# Telemetria.net
KiCad netlist of a schematic drawn in Altium Designer
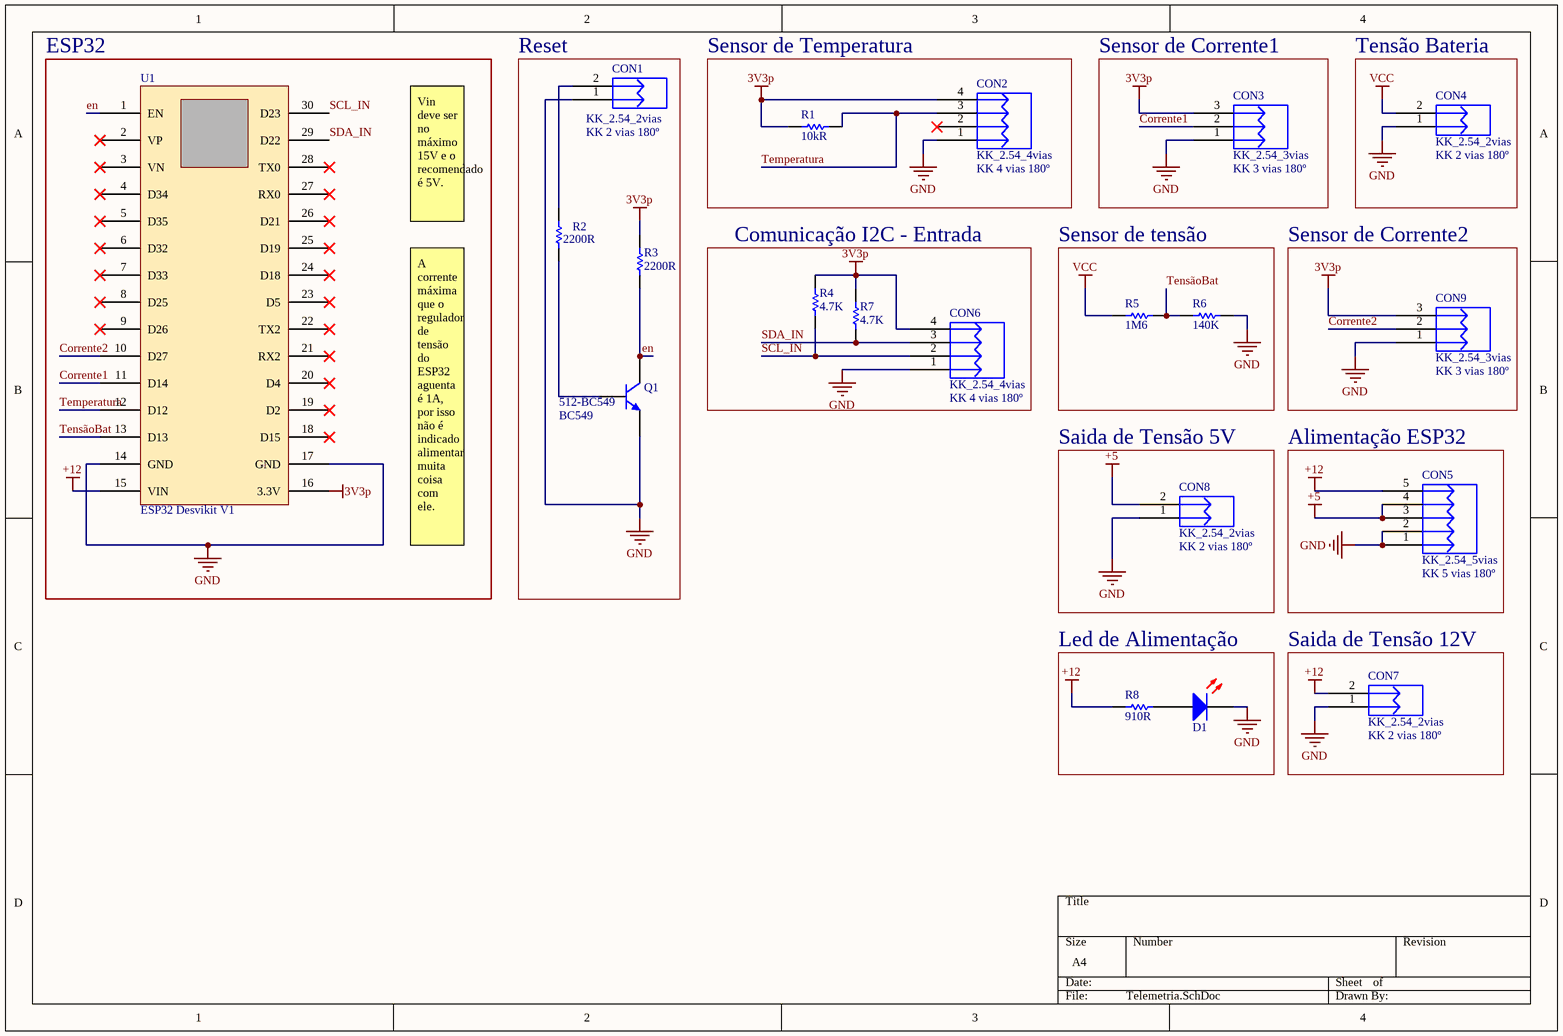
[diagram p0: Telemetria.SchDoc]

(export (version "E")
  (design (tool "Eeschema 10.0.6"))
  (components
    (comp (ref "CON1")
      (value "KK_2.54_2vias")
      (footprint "KK_2VIAS_180º")
      (description "Conector KK 2.54mm 2 vias")
      (fields (field (name "VALOR") "KK 2 vias 180º"))
      (libsource (lib "Conectores_Sch") (part "KK_2.54_2vias"))
    )
    (comp (ref "CON2")
      (value "KK_2.54_4vias")
      (footprint "KK_4vias_180°")
      (description "Conector KK 2.54mm 4 vias")
      (fields (field (name "VALOR") "KK 4 vias 180º"))
      (libsource (lib "Conectores_Sch") (part "KK_2.54_4vias"))
    )
    (comp (ref "CON3")
      (value "KK_2.54_3vias")
      (footprint "KK_3vias_180º")
      (description "Conector KK 2.54mm 3 vias")
      (fields (field (name "VALOR") "KK 3 vias 180º"))
      (libsource (lib "Conectores_Sch") (part "KK_2.54_3vias"))
    )
    (comp (ref "CON4")
      (value "KK_2.54_2vias")
      (footprint "KK_2VIAS_180º")
      (description "Conector KK 2.54mm 2 vias")
      (fields (field (name "VALOR") "KK 2 vias 180º"))
      (libsource (lib "Conectores_Sch") (part "KK_2.54_2vias"))
    )
    (comp (ref "CON5")
      (value "KK_2.54_5vias")
      (footprint "KK_5vias_180°")
      (description "Conector KK 2.54mm 5 vias")
      (fields (field (name "VALOR") "KK 5 vias 180º"))
      (libsource (lib "Conectores_Sch") (part "KK_2.54_5vias"))
    )
    (comp (ref "CON6")
      (value "KK_2.54_4vias")
      (footprint "KK_4vias_180°")
      (description "Conector KK 2.54mm 4 vias")
      (fields (field (name "VALOR") "KK 4 vias 180º"))
      (libsource (lib "Conectores_Sch") (part "KK_2.54_4vias"))
    )
    (comp (ref "CON7")
      (value "KK_2.54_2vias")
      (footprint "KK_2VIAS_180º")
      (description "Conector KK 2.54mm 2 vias")
      (fields (field (name "VALOR") "KK 2 vias 180º"))
      (libsource (lib "Conectores_Sch") (part "KK_2.54_2vias"))
    )
    (comp (ref "CON8")
      (value "KK_2.54_2vias")
      (footprint "KK_2VIAS_180º")
      (description "Conector KK 2.54mm 2 vias")
      (fields (field (name "VALOR") "KK 2 vias 180º"))
      (libsource (lib "Conectores_Sch") (part "KK_2.54_2vias"))
    )
    (comp (ref "CON9")
      (value "KK_2.54_3vias")
      (footprint "KK_3vias_180º")
      (description "Conector KK 2.54mm 3 vias")
      (fields (field (name "VALOR") "KK 3 vias 180º"))
      (libsource (lib "Conectores_Sch") (part "KK_2.54_3vias"))
    )
    (comp (ref "D1")
      (value "LED 5MM RED")
      (footprint "LED 5MM RED")
      (fields (field (name "MANUFACTURER") "Paralight") (field (name "MANUFACTURER PART NUMBER") "IMP585"))
      (libsource (lib "esp32") (part "LED 5MM RED"))
    )
    (comp (ref "Q1")
      (value "BC549")
      (footprint "TO92")
      (description "TRANS NPN 30V 0.1A TO-92")
      (fields
        (field (name "MANUFACTURER") "Fairchild Semiconductor")
        (field (name "SUPPLIER PART NUMBER 1") "512-BC549")
      )
      (libsource (lib "PS_Balanca") (part "BC549"))
    )
    (comp (ref "R1")
      (value "RES 470R 1/4W CARBON FILM")
      (footprint "RES 470R 1/4W CARBON FILM")
      (description "RES 470R OHM 1/4W 5% CARBON FILM")
      (fields
        (field (name "MANUFACTURER") "Ty-Ohm")
        (field (name "MANUFACTURER PART NUMBER") "CR25")
        (field (name "RESISTANCE (OHMS)") "10kR")
      )
      (libsource (lib "esp32") (part "RES 470R 1/4W CARBON FILM"))
    )
    (comp (ref "R2")
      (value "RES 470R 1/4W CARBON FILM")
      (footprint "RES 470R 1/4W CARBON FILM")
      (description "RES 470R OHM 1/4W 5% CARBON FILM")
      (fields
        (field (name "MANUFACTURER") "Ty-Ohm")
        (field (name "MANUFACTURER PART NUMBER") "CR25")
        (field (name "RESISTANCE (OHMS)") "2200R")
      )
      (libsource (lib "esp32") (part "RES 470R 1/4W CARBON FILM"))
    )
    (comp (ref "R3")
      (value "RES 470R 1/4W CARBON FILM")
      (footprint "RES 470R 1/4W CARBON FILM")
      (description "RES 470R OHM 1/4W 5% CARBON FILM")
      (fields
        (field (name "MANUFACTURER") "Ty-Ohm")
        (field (name "MANUFACTURER PART NUMBER") "CR25")
        (field (name "RESISTANCE (OHMS)") "2200R")
      )
      (libsource (lib "esp32") (part "RES 470R 1/4W CARBON FILM"))
    )
    (comp (ref "R4")
      (value "4.7K")
      (footprint "RES 4.7K 1/4W CARBON FILM")
      (description "RES 4.7K OHM 1/4W 5% CARBON FILM")
      (fields (field (name "MANUFACTURER") "Ty-Ohm") (field (name "MANUFACTURER PART NUMBER") "CR25"))
      (libsource (lib "esp32") (part "RES 4.7K 1/4W CARBON FILM"))
    )
    (comp (ref "R5")
      (value "1M6")
      (footprint "RESISTOR 0603")
      (fields
        (field (name "MANUFACTURER") "PANASONIC ELECTRONIC COMPONENTS")
        (field (name "MANUFACTURER PART NUMBER") "ERJ-3GEY0R00V")
        (field (name "TOLERANCE") "Jumper")
      )
      (libsource (lib "Resistores_SCHLIB") (part "RES 0R 5% 0603"))
    )
    (comp (ref "R6")
      (value "140K")
      (footprint "RESISTOR 0805")
      (fields
        (field (name "MANUFACTURER") "Panasonic")
        (field (name "MANUFACTURER PART NUMBER") "ERJP06F2200V")
      )
      (libsource (lib "Resistores_SCHLIB") (part "RES 220R 0805"))
    )
    (comp (ref "R7")
      (value "4.7K")
      (footprint "RES 4.7K 1/4W CARBON FILM")
      (description "RES 4.7K OHM 1/4W 5% CARBON FILM")
      (fields (field (name "MANUFACTURER") "Ty-Ohm") (field (name "MANUFACTURER PART NUMBER") "CR25"))
      (libsource (lib "esp32") (part "RES 4.7K 1/4W CARBON FILM"))
    )
    (comp (ref "R8")
      (value "RES 470R 1/4W CARBON FILM")
      (footprint "RES 470R 1/4W CARBON FILM")
      (description "RES 470R OHM 1/4W 5% CARBON FILM")
      (fields
        (field (name "MANUFACTURER") "Ty-Ohm")
        (field (name "MANUFACTURER PART NUMBER") "CR25")
        (field (name "RESISTANCE (OHMS)") "910R")
      )
      (libsource (lib "esp32") (part "RES 470R 1/4W CARBON FILM"))
    )
    (comp (ref "U1")
      (value "ESP32 Desvikit V1")
      (footprint "ESP32_Desvikit_v1")
      (description "microcontrolador com moculo bluethoth e wifi")
      (fields (field (name "Comment") "microcontrolador"))
      (libsource (lib "esp32") (part "ESP32 Desvikit v1"))
    )
  )
  (nets
    (net (code "1") (name "+5") (class "Default")
      (node (ref "CON5") (pin "3") (pintype "passive"))
      (node (ref "CON5") (pin "4") (pintype "passive"))
      (node (ref "CON8") (pin "2") (pintype "passive"))
    )
    (net (code "2") (name "+12") (class "Default")
      (node (ref "CON5") (pin "5") (pintype "passive"))
      (node (ref "CON7") (pin "2") (pintype "passive"))
      (node (ref "R8") (pin "2") (pinfunction "2_2") (pintype "passive"))
      (node (ref "U1") (pin "15") (pinfunction "VIN_15") (pintype "passive"))
    )
    (net (code "3") (name "/Corrente1") (class "Default")
      (node (ref "CON3") (pin "2") (pintype "passive"))
      (node (ref "U1") (pin "11") (pinfunction "D14_11") (pintype "passive"))
    )
    (net (code "4") (name "/Corrente2") (class "Default")
      (node (ref "CON9") (pin "2") (pintype "passive"))
      (node (ref "U1") (pin "10") (pinfunction "D27_10") (pintype "passive"))
    )
    (net (code "5") (name "/SCL_IN") (class "Default")
      (node (ref "CON6") (pin "2") (pintype "passive"))
      (node (ref "R4") (pin "2") (pinfunction "2_2") (pintype "passive"))
      (node (ref "U1") (pin "30") (pinfunction "D23_30") (pintype "passive"))
    )
    (net (code "6") (name "/SDA_IN") (class "Default")
      (node (ref "CON6") (pin "3") (pintype "passive"))
      (node (ref "R7") (pin "2") (pinfunction "2_2") (pintype "passive"))
      (node (ref "U1") (pin "29") (pinfunction "D22_29") (pintype "passive"))
    )
    (net (code "7") (name "/Temperatura") (class "Default")
      (node (ref "CON2") (pin "3") (pintype "passive"))
      (node (ref "R1") (pin "2") (pinfunction "2_2") (pintype "passive"))
      (node (ref "U1") (pin "12") (pinfunction "D12_12") (pintype "passive"))
    )
    (net (code "8") (name "/TensãoBat") (class "Default")
      (node (ref "R5") (pin "2") (pinfunction "2_2") (pintype "passive"))
      (node (ref "R6") (pin "1") (pinfunction "1_1") (pintype "passive"))
      (node (ref "U1") (pin "13") (pinfunction "D13_13") (pintype "passive"))
    )
    (net (code "9") (name "/en") (class "Default")
      (node (ref "Q1") (pin "1") (pinfunction "C_1") (pintype "passive"))
      (node (ref "R3") (pin "1") (pinfunction "1_1") (pintype "passive"))
      (node (ref "U1") (pin "1") (pinfunction "EN_1") (pintype "passive"))
    )
    (net (code "10") (name "3V3p") (class "Default")
      (node (ref "CON2") (pin "4") (pintype "passive"))
      (node (ref "CON3") (pin "3") (pintype "passive"))
      (node (ref "CON6") (pin "4") (pintype "passive"))
      (node (ref "CON9") (pin "3") (pintype "passive"))
      (node (ref "R1") (pin "1") (pinfunction "1_1") (pintype "passive"))
      (node (ref "R3") (pin "2") (pinfunction "2_2") (pintype "passive"))
      (node (ref "R4") (pin "1") (pinfunction "1_1") (pintype "passive"))
      (node (ref "R7") (pin "1") (pinfunction "1_1") (pintype "passive"))
      (node (ref "U1") (pin "16") (pinfunction "3.3V_16") (pintype "passive"))
    )
    (net (code "11") (name "GND") (class "Default")
      (node (ref "CON1") (pin "1") (pintype "passive"))
      (node (ref "CON2") (pin "1") (pintype "passive"))
      (node (ref "CON3") (pin "1") (pintype "passive"))
      (node (ref "CON4") (pin "1") (pintype "passive"))
      (node (ref "CON5") (pin "1") (pintype "passive"))
      (node (ref "CON5") (pin "2") (pintype "passive"))
      (node (ref "CON6") (pin "1") (pintype "passive"))
      (node (ref "CON7") (pin "1") (pintype "passive"))
      (node (ref "CON8") (pin "1") (pintype "passive"))
      (node (ref "CON9") (pin "1") (pintype "passive"))
      (node (ref "D1") (pin "2") (pinfunction "K_2") (pintype "passive"))
      (node (ref "Q1") (pin "3") (pinfunction "E_3") (pintype "passive"))
      (node (ref "R6") (pin "2") (pinfunction "2_2") (pintype "passive"))
      (node (ref "U1") (pin "14") (pinfunction "GND_14") (pintype "passive"))
      (node (ref "U1") (pin "17") (pinfunction "GND_17") (pintype "passive"))
    )
    (net (code "12") (name "Net-(CON1-Pad2)") (class "Default")
      (node (ref "CON1") (pin "2") (pintype "passive"))
      (node (ref "R2") (pin "2") (pinfunction "2_2") (pintype "passive"))
    )
    (net (code "13") (name "Net-(D1-A)") (class "Default")
      (node (ref "D1") (pin "1") (pinfunction "A_1") (pintype "passive"))
      (node (ref "R8") (pin "1") (pinfunction "1_1") (pintype "passive"))
    )
    (net (code "14") (name "Net-(Q1-B)") (class "Default")
      (node (ref "Q1") (pin "2") (pinfunction "B_2") (pintype "passive"))
      (node (ref "R2") (pin "1") (pinfunction "1_1") (pintype "passive"))
    )
    (net (code "15") (name "VCC") (class "Default")
      (node (ref "CON4") (pin "2") (pintype "passive"))
      (node (ref "R5") (pin "1") (pinfunction "1_1") (pintype "passive"))
    )
    (net (code "16") (name "unconnected-(CON2-Pad2)") (class "Default")
      (node (ref "CON2") (pin "2") (pintype "passive+no_connect"))
    )
    (net (code "17") (name "unconnected-(U1-D2-Pad19)") (class "Default")
      (node (ref "U1") (pin "19") (pinfunction "D2_19") (pintype "passive+no_connect"))
    )
    (net (code "18") (name "unconnected-(U1-D4-Pad20)") (class "Default")
      (node (ref "U1") (pin "20") (pinfunction "D4_20") (pintype "passive+no_connect"))
    )
    (net (code "19") (name "unconnected-(U1-D5-Pad23)") (class "Default")
      (node (ref "U1") (pin "23") (pinfunction "D5_23") (pintype "passive+no_connect"))
    )
    (net (code "20") (name "unconnected-(U1-D15-Pad18)") (class "Default")
      (node (ref "U1") (pin "18") (pinfunction "D15_18") (pintype "passive+no_connect"))
    )
    (net (code "21") (name "unconnected-(U1-D18-Pad24)") (class "Default")
      (node (ref "U1") (pin "24") (pinfunction "D18_24") (pintype "passive+no_connect"))
    )
    (net (code "22") (name "unconnected-(U1-D19-Pad25)") (class "Default")
      (node (ref "U1") (pin "25") (pinfunction "D19_25") (pintype "passive+no_connect"))
    )
    (net (code "23") (name "unconnected-(U1-D21-Pad26)") (class "Default")
      (node (ref "U1") (pin "26") (pinfunction "D21_26") (pintype "passive+no_connect"))
    )
    (net (code "24") (name "unconnected-(U1-D25-Pad8)") (class "Default")
      (node (ref "U1") (pin "8") (pinfunction "D25_8") (pintype "passive+no_connect"))
    )
    (net (code "25") (name "unconnected-(U1-D26-Pad9)") (class "Default")
      (node (ref "U1") (pin "9") (pinfunction "D26_9") (pintype "passive+no_connect"))
    )
    (net (code "26") (name "unconnected-(U1-D32-Pad6)") (class "Default")
      (node (ref "U1") (pin "6") (pinfunction "D32_6") (pintype "passive+no_connect"))
    )
    (net (code "27") (name "unconnected-(U1-D33-Pad7)") (class "Default")
      (node (ref "U1") (pin "7") (pinfunction "D33_7") (pintype "passive+no_connect"))
    )
    (net (code "28") (name "unconnected-(U1-D34-Pad4)") (class "Default")
      (node (ref "U1") (pin "4") (pinfunction "D34_4") (pintype "passive+no_connect"))
    )
    (net (code "29") (name "unconnected-(U1-D35-Pad5)") (class "Default")
      (node (ref "U1") (pin "5") (pinfunction "D35_5") (pintype "passive+no_connect"))
    )
    (net (code "30") (name "unconnected-(U1-RX0-Pad27)") (class "Default")
      (node (ref "U1") (pin "27") (pinfunction "RX0_27") (pintype "passive+no_connect"))
    )
    (net (code "31") (name "unconnected-(U1-RX2-Pad21)") (class "Default")
      (node (ref "U1") (pin "21") (pinfunction "RX2_21") (pintype "passive+no_connect"))
    )
    (net (code "32") (name "unconnected-(U1-TX0-Pad28)") (class "Default")
      (node (ref "U1") (pin "28") (pinfunction "TX0_28") (pintype "passive+no_connect"))
    )
    (net (code "33") (name "unconnected-(U1-TX2-Pad22)") (class "Default")
      (node (ref "U1") (pin "22") (pinfunction "TX2_22") (pintype "passive+no_connect"))
    )
    (net (code "34") (name "unconnected-(U1-VN-Pad3)") (class "Default")
      (node (ref "U1") (pin "3") (pinfunction "VN_3") (pintype "passive+no_connect"))
    )
    (net (code "35") (name "unconnected-(U1-VP-Pad2)") (class "Default")
      (node (ref "U1") (pin "2") (pinfunction "VP_2") (pintype "passive+no_connect"))
    )
  )
)
